# Tx_OpAmp_Sch.net
KiCad netlist of a schematic drawn in Altium Designer
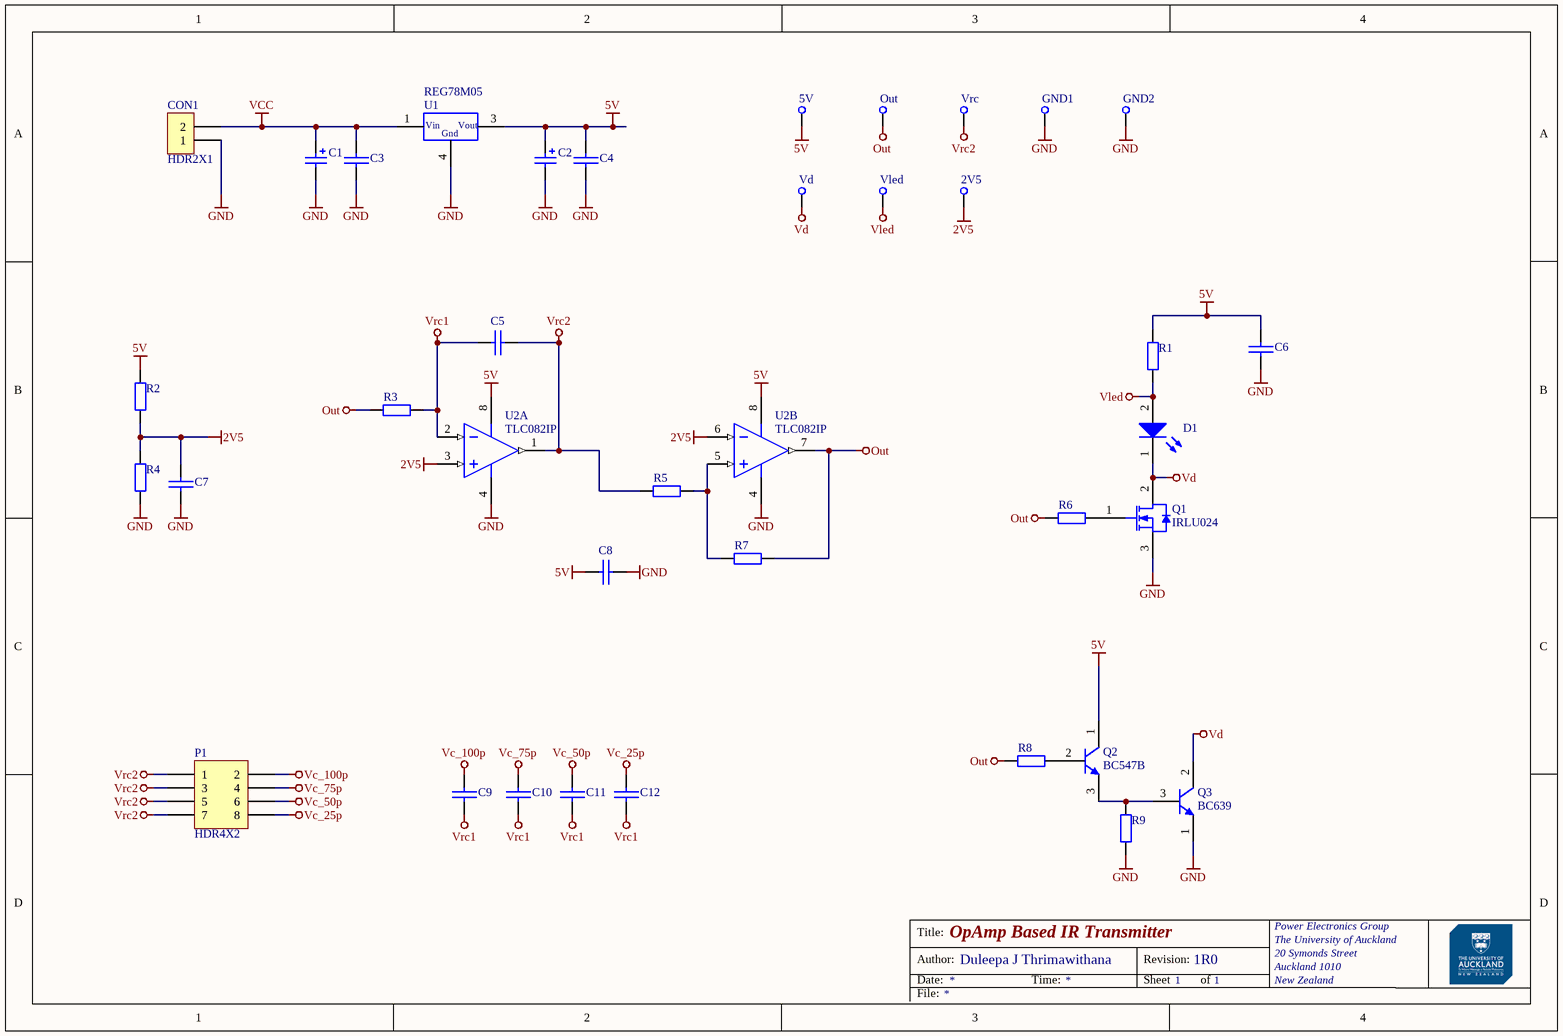
[diagram p0: Tx_OpAmp_Sch.SchDoc]

(export (version "E")
  (design (tool "Eeschema 10.0.6"))
  (components
    (comp (ref "2V5")
      (value "TP TH")
      (footprint "TP_TH_2.5mm")
      (fields (field (name "SOURCE") "UoAPE_Connectors and Mechanical.SchLib"))
      (libsource (lib "ECSE@UoA") (part "TP TH"))
    )
    (comp (ref "5V")
      (value "TP TH")
      (footprint "TP_TH_2.5mm")
      (fields (field (name "SOURCE") "UoAPE_Connectors and Mechanical.SchLib"))
      (libsource (lib "ECSE@UoA") (part "TP TH"))
    )
    (comp (ref "C1") (value "ECAP") (footprint "CR05") (libsource (lib "ECSE@UoA") (part "ECAP")))
    (comp (ref "C2") (value "ECAP") (footprint "CR05") (libsource (lib "ECSE@UoA") (part "ECAP")))
    (comp (ref "C3")
      (value "CCAP_TH_5P0")
      (footprint "CCAP_5P0")
      (description "TH ceramic cap with 5mm pitch")
      (libsource (lib "") (part "Symbol_1"))
    )
    (comp (ref "C4")
      (value "CCAP_TH_5P0")
      (footprint "CCAP_5P0")
      (description "TH ceramic cap with 5mm pitch")
      (libsource (lib "") (part "Symbol_1"))
    )
    (comp (ref "C5")
      (value "CCAP_TH_5P0")
      (footprint "CCAP_5P0")
      (description "TH ceramic cap with 5mm pitch")
      (libsource (lib "") (part "Symbol_1"))
    )
    (comp (ref "C6")
      (value "CCAP_TH_5P0")
      (footprint "CCAP_5P0")
      (description "TH ceramic cap with 5mm pitch")
      (libsource (lib "") (part "Symbol_1"))
    )
    (comp (ref "C7")
      (value "CCAP_TH_5P0")
      (footprint "CCAP_5P0")
      (description "TH ceramic cap with 5mm pitch")
      (libsource (lib "") (part "Symbol_1"))
    )
    (comp (ref "C8")
      (value "CCAP_TH_5P0")
      (footprint "CCAP_5P0")
      (description "TH ceramic cap with 5mm pitch")
      (libsource (lib "") (part "Symbol_1"))
    )
    (comp (ref "C9")
      (value "CCAP_TH_5P0")
      (footprint "CCAP_5P0")
      (description "TH ceramic cap with 5mm pitch")
      (libsource (lib "") (part "Symbol_1"))
    )
    (comp (ref "C10")
      (value "CCAP_TH_5P0")
      (footprint "CCAP_5P0")
      (description "TH ceramic cap with 5mm pitch")
      (libsource (lib "") (part "Symbol_1"))
    )
    (comp (ref "C11")
      (value "CCAP_TH_5P0")
      (footprint "CCAP_5P0")
      (description "TH ceramic cap with 5mm pitch")
      (libsource (lib "") (part "Symbol_1"))
    )
    (comp (ref "C12")
      (value "CCAP_TH_5P0")
      (footprint "CCAP_5P0")
      (description "TH ceramic cap with 5mm pitch")
      (libsource (lib "") (part "Symbol_1"))
    )
    (comp (ref "CON1")
      (value "HDR2X1")
      (footprint "HDR2X1_2P54")
      (description "Header 2X1")
      (libsource (lib "ECSE@UoA") (part "HDR2X1"))
    )
    (comp (ref "D1")
      (value "LED_TH")
      (footprint "TH_LED")
      (description "LED RED TH")
      (libsource (lib "ECSE@UoA") (part "8706943c75ba83719d021d2fdc84c58"))
    )
    (comp (ref "GND1")
      (value "TP TH")
      (footprint "TP_TH_2.5mm")
      (fields (field (name "SOURCE") "UoAPE_Connectors and Mechanical.SchLib"))
      (libsource (lib "ECSE@UoA") (part "TP TH"))
    )
    (comp (ref "GND2")
      (value "TP TH")
      (footprint "TP_TH_2.5mm")
      (fields (field (name "SOURCE") "UoAPE_Connectors and Mechanical.SchLib"))
      (libsource (lib "ECSE@UoA") (part "TP TH"))
    )
    (comp (ref "Out")
      (value "TP TH")
      (footprint "TP_TH_2.5mm")
      (fields (field (name "SOURCE") "UoAPE_Connectors and Mechanical.SchLib"))
      (libsource (lib "ECSE@UoA") (part "TP TH"))
    )
    (comp (ref "P1")
      (value "HDR4X2")
      (footprint "HDR4X2-2P54")
      (description "Header, 8-Pin, Dual row")
      (libsource (lib "ECSE@UoA") (part "HDR4x2"))
    )
    (comp (ref "Q1")
      (value "IRLU024")
      (footprint "FP-PG-TO251-3-MFG")
      (libsource (lib "ECSE@UoA") (part "535c4fe1372f32a24686ada0a8c11ba"))
    )
    (comp (ref "Q2")
      (value "BC547B")
      (footprint "ONSC-TO-92-3-29-11")
      (description "Small Signal Bipolar Transistor, 0.1A I(C), 45V V(BR)CEO, 1-Element, NPN, Silicon, TO-92")
      (libsource (lib "ECSE@UoA") (part "ONSC-NPN-C1B2E3-3"))
    )
    (comp (ref "Q3")
      (value "BC639")
      (footprint "ONSC-TO-92-3-29-11")
      (description "Small Signal Bipolar Transistor, 1A I(C), 80V V(BR)CEO, 1-Element, NPN, Silicon, TO-92")
      (libsource (lib "ECSE@UoA") (part "ONSC-NPN-E1C2B3-3"))
    )
    (comp (ref "R1")
      (value "RESAX4")
      (footprint "RAX4")
      (description "Axial Resistor")
      (libsource (lib "") (part "Symbol_4"))
    )
    (comp (ref "R2")
      (value "RESAX4")
      (footprint "RAX4")
      (description "Axial Resistor")
      (libsource (lib "") (part "Symbol_2"))
    )
    (comp (ref "R3")
      (value "RESAX4")
      (footprint "RAX4")
      (description "Axial Resistor")
      (libsource (lib "") (part "Symbol_3"))
    )
    (comp (ref "R4")
      (value "RESAX4")
      (footprint "RAX4")
      (description "Axial Resistor")
      (libsource (lib "") (part "Symbol_2"))
    )
    (comp (ref "R5")
      (value "RESAX4")
      (footprint "RAX4")
      (description "Axial Resistor")
      (libsource (lib "") (part "Symbol_3"))
    )
    (comp (ref "R6")
      (value "RESAX4")
      (footprint "RAX4")
      (description "Axial Resistor")
      (libsource (lib "") (part "Symbol_3"))
    )
    (comp (ref "R7")
      (value "RESAX4")
      (footprint "RAX4")
      (description "Axial Resistor")
      (libsource (lib "") (part "Symbol_3"))
    )
    (comp (ref "R8")
      (value "RESAX4")
      (footprint "RAX4")
      (description "Axial Resistor")
      (libsource (lib "ECSE@UoA") (part "Symbol"))
    )
    (comp (ref "R9")
      (value "RESAX4")
      (footprint "RAX4")
      (description "Axial Resistor")
      (libsource (lib "") (part "Symbol_2"))
    )
    (comp (ref "U1")
      (value "REG78M05")
      (footprint "TO220_Reg")
      (description "78M Series Linear Regulators")
      (libsource (lib "ECSE@UoA") (part "REG78MXX"))
    )
    (comp (ref "U2")
      (value "TLC082IP")
      (footprint "P0008A")
      (description "Operational Amplifier, 2 Func, 3000uV Offset-Max, BIMOS, PDIP8")
      (fields (field (name "POWER") "100mW"))
      (libsource (lib "ECSE@UoA") (part "TI-TLV_TLC-8"))
    )
    (comp (ref "Vd")
      (value "TP TH")
      (footprint "TP_TH_2.5mm")
      (fields (field (name "SOURCE") "UoAPE_Connectors and Mechanical.SchLib"))
      (libsource (lib "ECSE@UoA") (part "TP TH"))
    )
    (comp (ref "Vled")
      (value "TP TH")
      (footprint "TP_TH_2.5mm")
      (fields (field (name "SOURCE") "UoAPE_Connectors and Mechanical.SchLib"))
      (libsource (lib "ECSE@UoA") (part "TP TH"))
    )
    (comp (ref "Vrc")
      (value "TP TH")
      (footprint "TP_TH_2.5mm")
      (fields (field (name "SOURCE") "UoAPE_Connectors and Mechanical.SchLib"))
      (libsource (lib "ECSE@UoA") (part "TP TH"))
    )
  )
  (nets
    (net (code "1") (name "2V5") (class "Default")
      (node (ref "2V5") (pin "1") (pinfunction "1_1") (pintype "passive"))
      (node (ref "C7") (pin "1") (pinfunction "1_1") (pintype "passive"))
      (node (ref "R2") (pin "2") (pinfunction "2_2") (pintype "passive"))
      (node (ref "R4") (pin "1") (pinfunction "1_1") (pintype "passive"))
      (node (ref "U2") (pin "3") (pinfunction "IN1+_3") (pintype "input"))
      (node (ref "U2") (pin "6") (pinfunction "IN2-_6") (pintype "input"))
    )
    (net (code "2") (name "5V") (class "Default")
      (node (ref "5V") (pin "1") (pinfunction "1_1") (pintype "passive"))
      (node (ref "C2") (pin "1") (pinfunction "1_1") (pintype "passive"))
      (node (ref "C4") (pin "2") (pinfunction "2_2") (pintype "passive"))
      (node (ref "C6") (pin "2") (pinfunction "2_2") (pintype "passive"))
      (node (ref "C8") (pin "2") (pinfunction "2_2") (pintype "passive"))
      (node (ref "Q2") (pin "1") (pinfunction "C_1") (pintype "passive"))
      (node (ref "R1") (pin "2") (pinfunction "2_2") (pintype "passive"))
      (node (ref "R2") (pin "1") (pinfunction "1_1") (pintype "passive"))
      (node (ref "U1") (pin "3") (pinfunction "Vout_3") (pintype "passive"))
      (node (ref "U2") (pin "8") (pinfunction "VDD_8") (pintype "power_in"))
    )
    (net (code "3") (name "GND") (class "Default")
      (node (ref "C1") (pin "2") (pinfunction "2_2") (pintype "passive"))
      (node (ref "C2") (pin "2") (pinfunction "2_2") (pintype "passive"))
      (node (ref "C3") (pin "1") (pinfunction "1_1") (pintype "passive"))
      (node (ref "C4") (pin "1") (pinfunction "1_1") (pintype "passive"))
      (node (ref "C6") (pin "1") (pinfunction "1_1") (pintype "passive"))
      (node (ref "C7") (pin "2") (pinfunction "2_2") (pintype "passive"))
      (node (ref "C8") (pin "1") (pinfunction "1_1") (pintype "passive"))
      (node (ref "CON1") (pin "1") (pinfunction "1_1") (pintype "passive"))
      (node (ref "GND1") (pin "1") (pinfunction "1_1") (pintype "passive"))
      (node (ref "GND2") (pin "1") (pinfunction "1_1") (pintype "passive"))
      (node (ref "Q1") (pin "3") (pinfunction "SOURCE_3") (pintype "passive"))
      (node (ref "Q3") (pin "1") (pinfunction "E_1") (pintype "passive"))
      (node (ref "R4") (pin "2") (pinfunction "2_2") (pintype "passive"))
      (node (ref "R9") (pin "2") (pinfunction "2_2") (pintype "passive"))
      (node (ref "U1") (pin "4") (pinfunction "Gnd_4") (pintype "passive"))
      (node (ref "U2") (pin "4") (pinfunction "GND_4") (pintype "power_in"))
    )
    (net (code "4") (name "Net-(Q1-GATE)") (class "Default")
      (node (ref "Q1") (pin "1") (pinfunction "GATE_1") (pintype "passive"))
      (node (ref "R6") (pin "1") (pinfunction "1_1") (pintype "passive"))
    )
    (net (code "5") (name "Net-(Q2-B)") (class "Default")
      (node (ref "Q2") (pin "2") (pinfunction "B_2") (pintype "passive"))
      (node (ref "R8") (pin "2") (pinfunction "2_2") (pintype "passive"))
    )
    (net (code "6") (name "Net-(Q2-E)") (class "Default")
      (node (ref "Q2") (pin "3") (pinfunction "E_3") (pintype "passive"))
      (node (ref "Q3") (pin "3") (pinfunction "B_3") (pintype "passive"))
      (node (ref "R9") (pin "1") (pinfunction "1_1") (pintype "passive"))
    )
    (net (code "7") (name "Net-(U2B-IN2+)") (class "Default")
      (node (ref "R5") (pin "1") (pinfunction "1_1") (pintype "passive"))
      (node (ref "R7") (pin "2") (pinfunction "2_2") (pintype "passive"))
      (node (ref "U2") (pin "5") (pinfunction "IN2+_5") (pintype "input"))
    )
    (net (code "8") (name "Out") (class "Default")
      (node (ref "Out") (pin "1") (pinfunction "1_1") (pintype "passive"))
      (node (ref "R3") (pin "2") (pinfunction "2_2") (pintype "passive"))
      (node (ref "R6") (pin "2") (pinfunction "2_2") (pintype "passive"))
      (node (ref "R7") (pin "1") (pinfunction "1_1") (pintype "passive"))
      (node (ref "R8") (pin "1") (pinfunction "1_1") (pintype "passive"))
      (node (ref "U2") (pin "7") (pinfunction "OUT2_7") (pintype "output"))
    )
    (net (code "9") (name "VCC") (class "Default")
      (node (ref "C1") (pin "1") (pinfunction "1_1") (pintype "passive"))
      (node (ref "C3") (pin "2") (pinfunction "2_2") (pintype "passive"))
      (node (ref "CON1") (pin "2") (pinfunction "2_2") (pintype "passive"))
      (node (ref "U1") (pin "1") (pinfunction "Vin_1") (pintype "passive"))
    )
    (net (code "10") (name "Vc_25p") (class "Default")
      (node (ref "C12") (pin "2") (pinfunction "2_2") (pintype "passive"))
      (node (ref "P1") (pin "8") (pinfunction "8_8") (pintype "passive"))
    )
    (net (code "11") (name "Vc_50p") (class "Default")
      (node (ref "C11") (pin "2") (pinfunction "2_2") (pintype "passive"))
      (node (ref "P1") (pin "6") (pinfunction "6_6") (pintype "passive"))
    )
    (net (code "12") (name "Vc_75p") (class "Default")
      (node (ref "C10") (pin "2") (pinfunction "2_2") (pintype "passive"))
      (node (ref "P1") (pin "4") (pinfunction "4_4") (pintype "passive"))
    )
    (net (code "13") (name "Vc_100p") (class "Default")
      (node (ref "C9") (pin "2") (pinfunction "2_2") (pintype "passive"))
      (node (ref "P1") (pin "2") (pinfunction "2_2") (pintype "passive"))
    )
    (net (code "14") (name "Vd") (class "Default")
      (node (ref "D1") (pin "1") (pinfunction "C_1") (pintype "passive"))
      (node (ref "Q1") (pin "2") (pinfunction "DRAIN_2") (pintype "passive"))
      (node (ref "Q3") (pin "2") (pinfunction "C_2") (pintype "passive"))
      (node (ref "Vd") (pin "1") (pinfunction "1_1") (pintype "passive"))
    )
    (net (code "15") (name "Vled") (class "Default")
      (node (ref "D1") (pin "2") (pinfunction "A_2") (pintype "passive"))
      (node (ref "R1") (pin "1") (pinfunction "1_1") (pintype "passive"))
      (node (ref "Vled") (pin "1") (pinfunction "1_1") (pintype "passive"))
    )
    (net (code "16") (name "Vrc1") (class "Default")
      (node (ref "C10") (pin "1") (pinfunction "1_1") (pintype "passive"))
      (node (ref "C11") (pin "1") (pinfunction "1_1") (pintype "passive"))
      (node (ref "C12") (pin "1") (pinfunction "1_1") (pintype "passive"))
      (node (ref "C5") (pin "2") (pinfunction "2_2") (pintype "passive"))
      (node (ref "C9") (pin "1") (pinfunction "1_1") (pintype "passive"))
      (node (ref "R3") (pin "1") (pinfunction "1_1") (pintype "passive"))
      (node (ref "U2") (pin "2") (pinfunction "IN1-_2") (pintype "input"))
    )
    (net (code "17") (name "Vrc2") (class "Default")
      (node (ref "C5") (pin "1") (pinfunction "1_1") (pintype "passive"))
      (node (ref "P1") (pin "1") (pinfunction "1_1") (pintype "passive"))
      (node (ref "P1") (pin "3") (pinfunction "3_3") (pintype "passive"))
      (node (ref "P1") (pin "5") (pinfunction "5_5") (pintype "passive"))
      (node (ref "P1") (pin "7") (pinfunction "7_7") (pintype "passive"))
      (node (ref "R5") (pin "2") (pinfunction "2_2") (pintype "passive"))
      (node (ref "U2") (pin "1") (pinfunction "OUT1_1") (pintype "output"))
      (node (ref "Vrc") (pin "1") (pinfunction "1_1") (pintype "passive"))
    )
  )
)
